# Adafruit_ESP32-S3_8MB_No_PSRAM.net
KiCad netlist of a schematic drawn in EAGLE
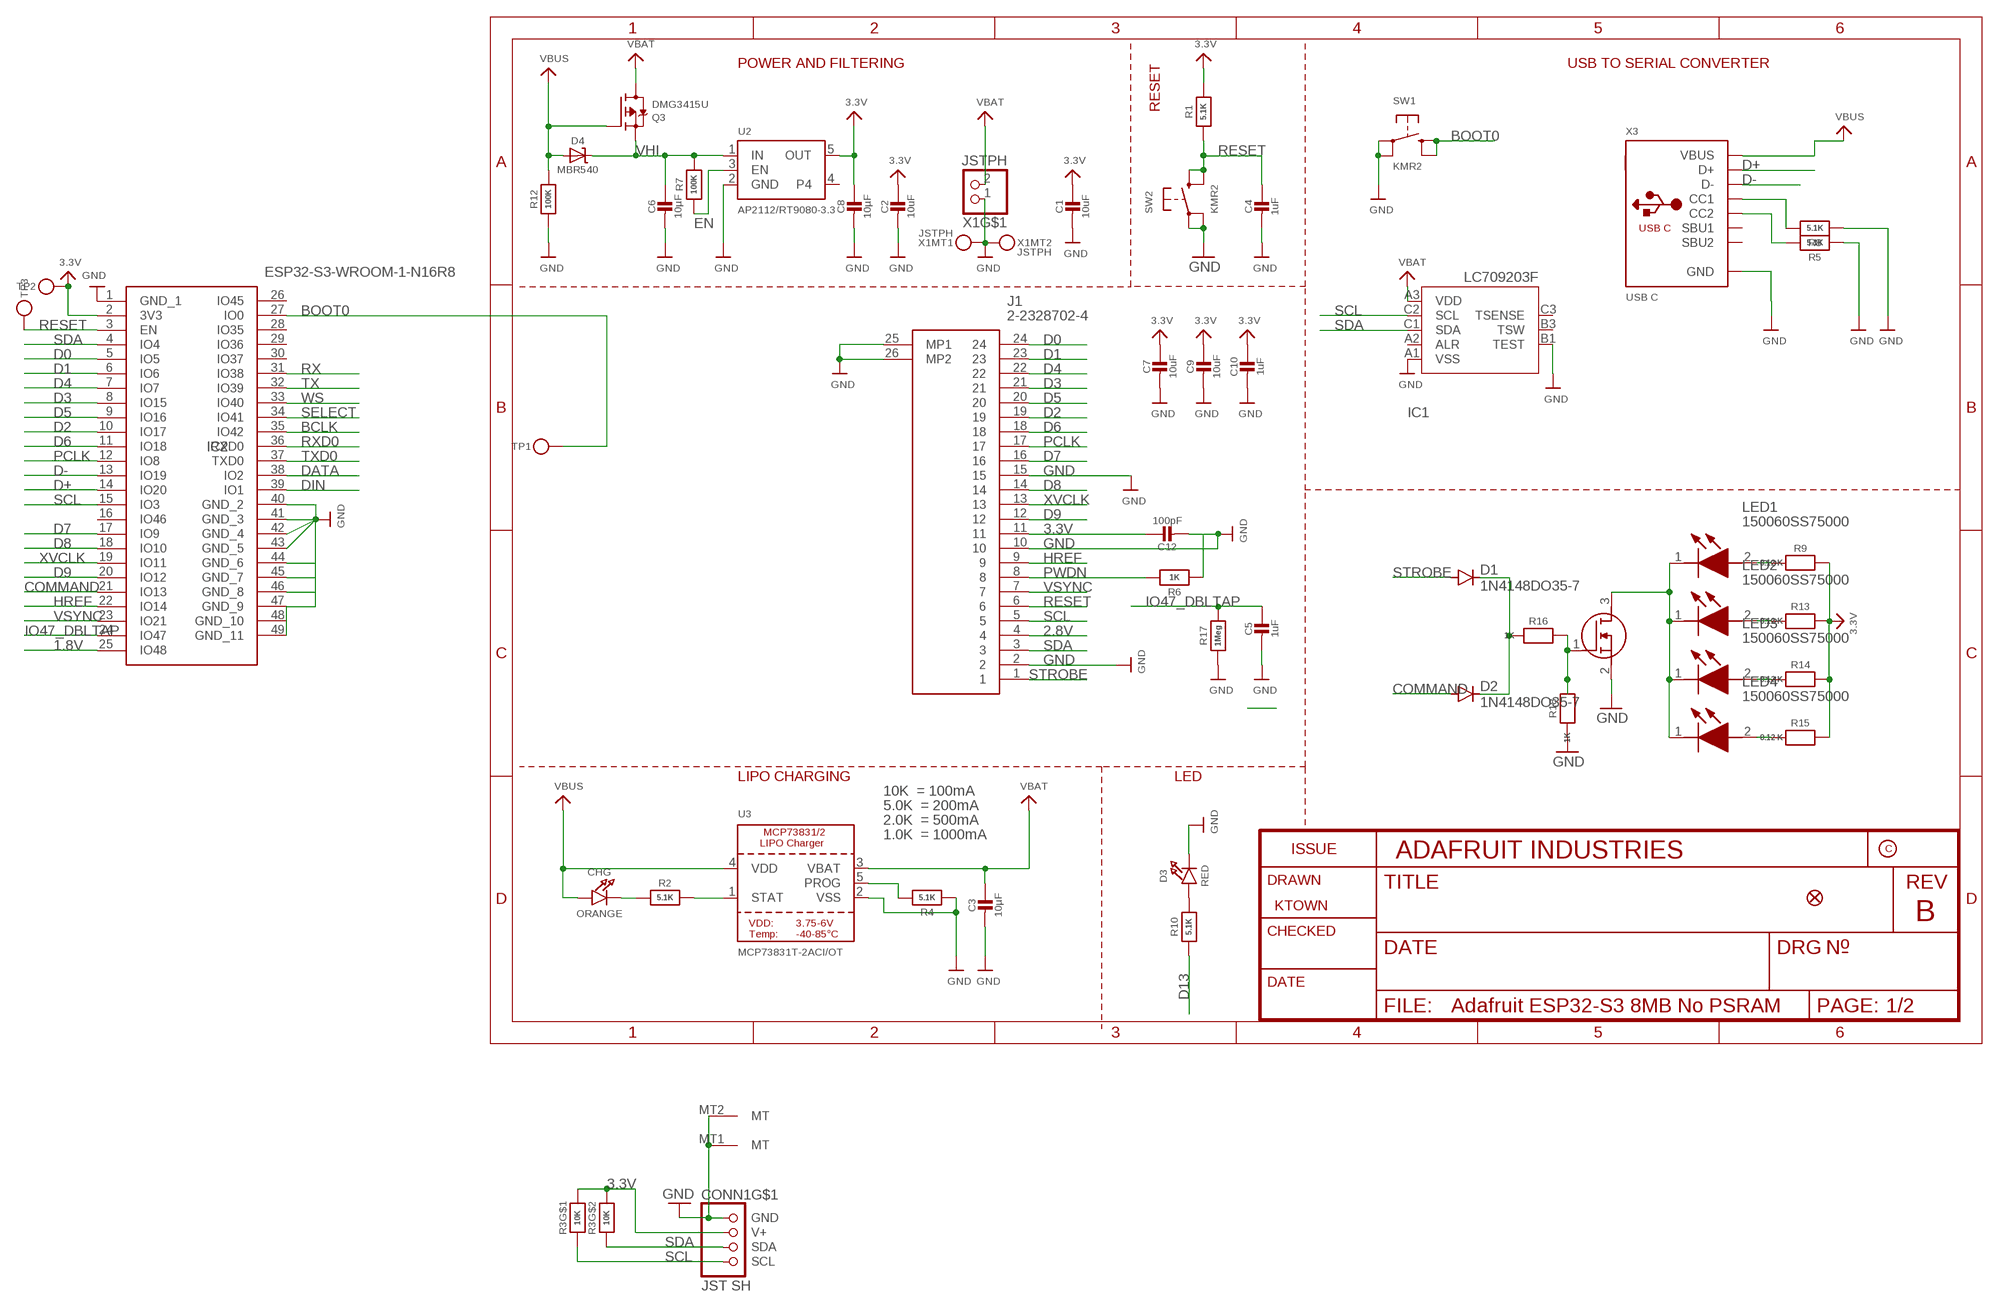
[diagram p0: schematic, sheet 1]
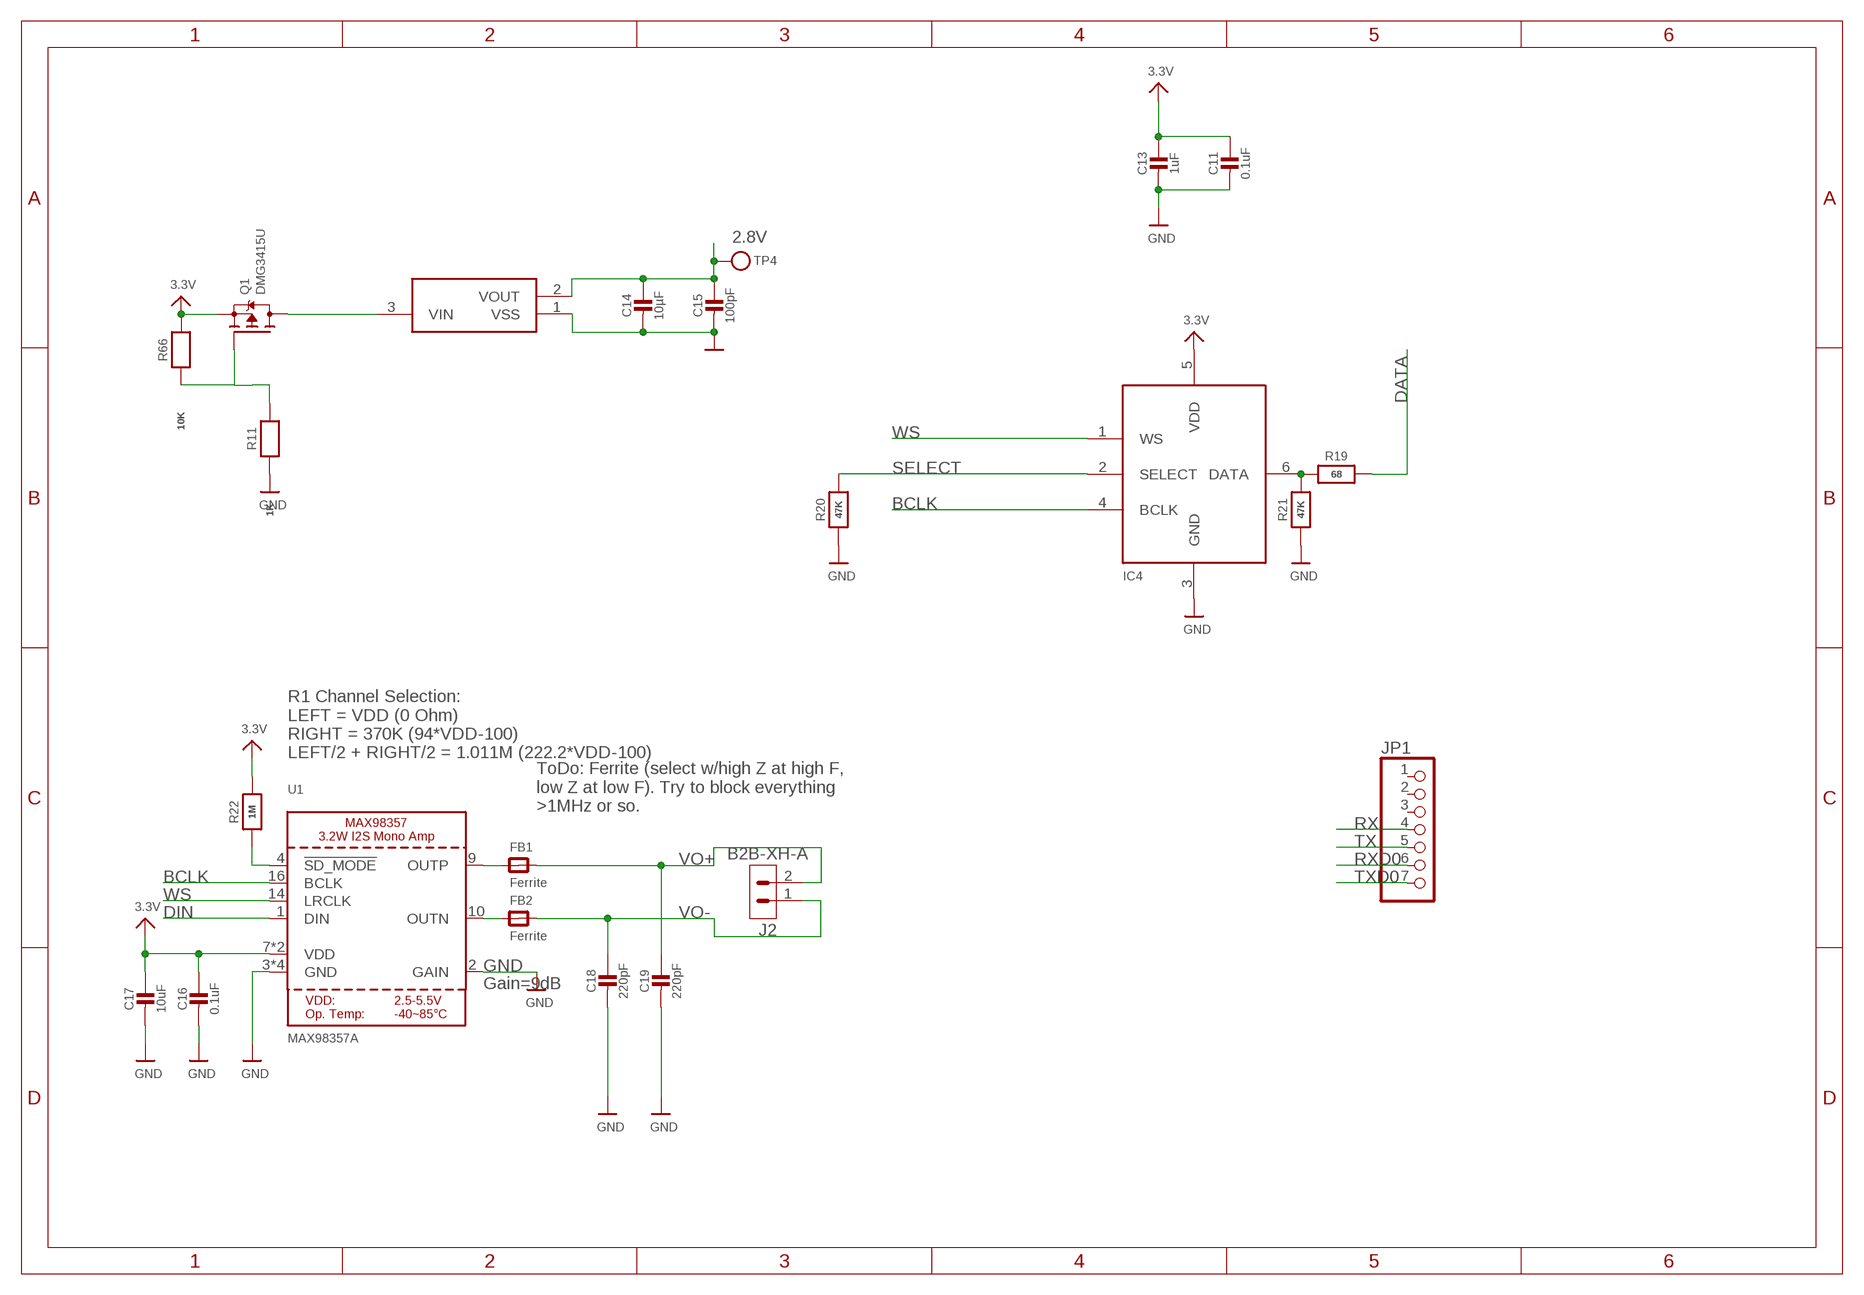
[diagram p1: schematic, sheet 2]

(export (version "E")
  (design (tool "Eeschema 10.0.6"))
  (components
    (comp (ref "C11")
      (value "0.1uF")
      (footprint "eagle-import:0603-NO")
      (libsource (lib "eagle-import") (part "CAP_CERAMIC0603_NO"))
    )
    (comp (ref "C13")
      (value "1uF")
      (footprint "eagle-import:0603-NO")
      (libsource (lib "eagle-import") (part "CAP_CERAMIC0603_NO"))
    )
    (comp (ref "C14")
      (value "10µF")
      (footprint "eagle-import:0805-NO")
      (libsource (lib "eagle-import") (part "CAP_CERAMIC0805-NOOUTLINE"))
    )
    (comp (ref "C15")
      (value "100pF")
      (footprint "eagle-import:0805-NO")
      (libsource (lib "eagle-import") (part "CAP_CERAMIC0805-NOOUTLINE"))
    )
    (comp (ref "C16")
      (value "0.1uF")
      (footprint "eagle-import:0805-NO")
      (libsource (lib "eagle-import") (part "CAP_CERAMIC0805-NOOUTLINE"))
    )
    (comp (ref "C17")
      (value "10uF")
      (footprint "eagle-import:0805-NO")
      (libsource (lib "eagle-import") (part "CAP_CERAMIC0805-NOOUTLINE"))
    )
    (comp (ref "C18")
      (value "220pF")
      (footprint "eagle-import:0805-NO")
      (libsource (lib "eagle-import") (part "CAP_CERAMIC0805-NOOUTLINE"))
    )
    (comp (ref "C19")
      (value "220pF")
      (footprint "eagle-import:0805-NO")
      (libsource (lib "eagle-import") (part "CAP_CERAMIC0805-NOOUTLINE"))
    )
    (comp (ref "FB1")
      (value "Ferrite")
      (footprint "eagle-import:0805-NO")
      (libsource (lib "eagle-import") (part "FERRITE-0805NO"))
    )
    (comp (ref "FB2")
      (value "Ferrite")
      (footprint "eagle-import:0805-NO")
      (libsource (lib "eagle-import") (part "FERRITE-0805NO"))
    )
    (comp (ref "IC3")
      (value "XC6206P282MR-G")
      (footprint "eagle-import:SOT95P280X130-3N")
      (fields (field (name "MOUSER_PART_NUMBER") "865-XC6206P282MR-G"))
      (libsource (lib "eagle-import") (part "XC6206P282MR-G"))
    )
    (comp (ref "IC4")
      (value "ICS-43434")
      (footprint "eagle-import:SPH0645LM4H")
      (libsource (lib "eagle-import") (part "MIC_I2S_SPH0645"))
    )
    (comp (ref "J2")
      (value "B2B-XH-A")
      (footprint "eagle-import:B2B-XH-A")
      (fields (field (name "MANUFACTURER") "JST Sales America Inc."))
      (libsource (lib "eagle-import") (part "B2B-XH-A"))
    )
    (comp (ref "JP1")
      (value "HEADER-1X7THICKER")
      (footprint "eagle-import:1X07_ROUND_76")
      (libsource (lib "eagle-import") (part "HEADER-1X7THICKER"))
    )
    (comp (ref "Q1")
      (value "DMG3415U")
      (footprint "eagle-import:SOT23-R")
      (libsource (lib "eagle-import") (part "MOSFET-P"))
    )
    (comp (ref "R11")
      (value "1K")
      (footprint "eagle-import:0603-NO")
      (libsource (lib "eagle-import") (part "RESISTOR_0603_NOOUT"))
    )
    (comp (ref "R19")
      (value "68")
      (footprint "eagle-import:0603-NO")
      (libsource (lib "eagle-import") (part "RESISTOR_0603_NOOUT"))
    )
    (comp (ref "R20")
      (value "47K")
      (footprint "eagle-import:0603-NO")
      (libsource (lib "eagle-import") (part "RESISTOR_0603_NOOUT"))
    )
    (comp (ref "R21")
      (value "47K")
      (footprint "eagle-import:0603-NO")
      (libsource (lib "eagle-import") (part "RESISTOR_0603_NOOUT"))
    )
    (comp (ref "R22")
      (value "1M")
      (footprint "eagle-import:0805-NO")
      (libsource (lib "eagle-import") (part "RESISTOR0805_NOOUTLINE"))
    )
    (comp (ref "R66")
      (value "10K")
      (footprint "eagle-import:0603-NO")
      (libsource (lib "eagle-import") (part "RESISTOR_0603_NOOUT"))
    )
    (comp (ref "TP4")
      (value "TESTPOINTROUND1.5MMNO")
      (footprint "eagle-import:TESTPOINT_ROUND_1.5MM_NO")
      (libsource (lib "eagle-import") (part "TESTPOINTROUND1.5MMNO"))
    )
    (comp (ref "U1")
      (value "MAX98357A")
      (footprint "eagle-import:QFN16_3MM")
      (libsource (lib "eagle-import") (part "AUDIOAMP_MAX98357"))
    )
    (comp (ref "C1")
      (value "10uF")
      (footprint "eagle-import:0805-NO")
      (libsource (lib "eagle-import") (part "CAP_CERAMIC0805-NOOUTLINE"))
    )
    (comp (ref "C2")
      (value "10uF")
      (footprint "eagle-import:0805-NO")
      (libsource (lib "eagle-import") (part "CAP_CERAMIC0805-NOOUTLINE"))
    )
    (comp (ref "C3")
      (value "10µF")
      (footprint "eagle-import:0805-NO")
      (libsource (lib "eagle-import") (part "CAP_CERAMIC0805-NOOUTLINE"))
    )
    (comp (ref "C4")
      (value "1uF")
      (footprint "eagle-import:0603-NO")
      (libsource (lib "eagle-import") (part "CAP_CERAMIC0603_NO"))
    )
    (comp (ref "C5")
      (value "1uF")
      (footprint "eagle-import:0603-NO")
      (libsource (lib "eagle-import") (part "CAP_CERAMIC0603_NO"))
    )
    (comp (ref "C6")
      (value "10µF")
      (footprint "eagle-import:0805-NO")
      (libsource (lib "eagle-import") (part "CAP_CERAMIC0805-NOOUTLINE"))
    )
    (comp (ref "C7")
      (value "10uF")
      (footprint "eagle-import:0805-NO")
      (libsource (lib "eagle-import") (part "CAP_CERAMIC0805-NOOUTLINE"))
    )
    (comp (ref "C8")
      (value "10µF")
      (footprint "eagle-import:0805-NO")
      (fields (field (name "REV") "C"))
      (libsource (lib "eagle-import") (part "CAP_CERAMIC0805-NOOUTLINE"))
    )
    (comp (ref "C9")
      (value "10uF")
      (footprint "eagle-import:0805-NO")
      (libsource (lib "eagle-import") (part "CAP_CERAMIC0805-NOOUTLINE"))
    )
    (comp (ref "C10")
      (value "1uF")
      (footprint "eagle-import:0603-NO")
      (libsource (lib "eagle-import") (part "CAP_CERAMIC0603_NO"))
    )
    (comp (ref "C12")
      (value "100pF")
      (footprint "eagle-import:0805-NO")
      (libsource (lib "eagle-import") (part "CAP_CERAMIC0805-NOOUTLINE"))
    )
    (comp (ref "CHG")
      (value "ORANGE")
      (footprint "eagle-import:CHIPLED_0603_NOOUTLINE")
      (libsource (lib "eagle-import") (part "LED0603_NOOUTLINE"))
    )
    (comp (ref "CONN1")
      (value "JST SH")
      (footprint "eagle-import:JST_SH4_RA")
      (libsource (lib "eagle-import") (part "STEMMA_I2C_QTRA"))
    )
    (comp (ref "D1")
      (value "1N4148DO35-7")
      (footprint "eagle-import:DO35-7")
      (libsource (lib "eagle-import") (part "1N4148DO35-7"))
    )
    (comp (ref "D2")
      (value "1N4148DO35-7")
      (footprint "eagle-import:DO35-7")
      (libsource (lib "eagle-import") (part "1N4148DO35-7"))
    )
    (comp (ref "D3")
      (value "RED")
      (footprint "eagle-import:CHIPLED_0603_NOOUTLINE")
      (libsource (lib "eagle-import") (part "LED0603_NOOUTLINE"))
    )
    (comp (ref "D4")
      (value "MBR540")
      (footprint "eagle-import:SOD-123")
      (libsource (lib "eagle-import") (part "DIODE-SCHOTTKYSOD-123"))
    )
    (comp (ref "IC1")
      (value "LC709203F/MH")
      (footprint "eagle-import:WLCSP9")
      (libsource (lib "eagle-import") (part "LC709203F/MH"))
    )
    (comp (ref "IC2")
      (value "ESP32-S3-WROOM-1-N16R8")
      (footprint "eagle-import:ESP32S3WROOM1N16R8")
      (fields (field (name "MOUSER_PART_NUMBER") "356-ESP32S3WRM1N16R8"))
      (libsource (lib "eagle-import") (part "ESP32-S3-WROOM-1-N16R8"))
    )
    (comp (ref "J1")
      (value "2-2328702-4")
      (footprint "eagle-import:223287024")
      (fields (field (name "MOUSER_PART_NUMBER") "571-2-2328702-4"))
      (libsource (lib "eagle-import") (part "2-2328702-4"))
    )
    (comp (ref "LED1")
      (value "150060SS75000")
      (footprint "eagle-import:LEDC1608X80N")
      (fields (field (name "MOUSER_PART_NUMBER") "710-150060SS75000"))
      (libsource (lib "eagle-import") (part "150060SS75000"))
    )
    (comp (ref "LED2")
      (value "150060SS75000")
      (footprint "eagle-import:LEDC1608X80N")
      (fields (field (name "MOUSER_PART_NUMBER") "710-150060SS75000"))
      (libsource (lib "eagle-import") (part "150060SS75000"))
    )
    (comp (ref "LED3")
      (value "150060SS75000")
      (footprint "eagle-import:LEDC1608X80N")
      (fields (field (name "MOUSER_PART_NUMBER") "710-150060SS75000"))
      (libsource (lib "eagle-import") (part "150060SS75000"))
    )
    (comp (ref "LED4")
      (value "150060SS75000")
      (footprint "eagle-import:LEDC1608X80N")
      (fields (field (name "MOUSER_PART_NUMBER") "710-150060SS75000"))
      (libsource (lib "eagle-import") (part "150060SS75000"))
    )
    (comp (ref "Q2")
      (value "2N7002")
      (footprint "eagle-import:SOT96P240X120-3N")
      (fields (field (name "MOUSER_PART_NUMBER") "512-2N7002"))
      (libsource (lib "eagle-import") (part "2N7002"))
    )
    (comp (ref "Q3")
      (value "DMG3415U")
      (footprint "eagle-import:SOT23-R")
      (libsource (lib "eagle-import") (part "MOSFET-P"))
    )
    (comp (ref "R1")
      (value "5.1K")
      (footprint "eagle-import:0603-NO")
      (libsource (lib "eagle-import") (part "RESISTOR_0603_NOOUT"))
    )
    (comp (ref "R2")
      (value "5.1K")
      (footprint "eagle-import:0603-NO")
      (libsource (lib "eagle-import") (part "RESISTOR_0603_NOOUT"))
    )
    (comp (ref "R3")
      (value "10K")
      (footprint "eagle-import:RESPACK_4X0603")
      (libsource (lib "eagle-import") (part "RESISTOR_4PACK"))
    )
    (comp (ref "R4")
      (value "5.1K")
      (footprint "eagle-import:0603-NO")
      (libsource (lib "eagle-import") (part "RESISTOR_0603_NOOUT"))
    )
    (comp (ref "R5")
      (value "5.1K")
      (footprint "eagle-import:0603-NO")
      (libsource (lib "eagle-import") (part "RESISTOR_0603_NOOUT"))
    )
    (comp (ref "R6")
      (value "1K")
      (footprint "eagle-import:0603-NO")
      (libsource (lib "eagle-import") (part "RESISTOR_0603_NOOUT"))
    )
    (comp (ref "R7")
      (value "100K")
      (footprint "eagle-import:0603-NO")
      (libsource (lib "eagle-import") (part "RESISTOR_0603_NOOUT"))
    )
    (comp (ref "R8")
      (value "5.1K")
      (footprint "eagle-import:0603-NO")
      (libsource (lib "eagle-import") (part "RESISTOR_0603_NOOUT"))
    )
    (comp (ref "R9")
      (value "0.12 K")
      (footprint "eagle-import:0603-NO")
      (libsource (lib "eagle-import") (part "RESISTOR_0603_NOOUT"))
    )
    (comp (ref "R10")
      (value "5.1K")
      (footprint "eagle-import:0603-NO")
      (libsource (lib "eagle-import") (part "RESISTOR_0603_NOOUT"))
    )
    (comp (ref "R12")
      (value "100K")
      (footprint "eagle-import:0603-NO")
      (libsource (lib "eagle-import") (part "RESISTOR_0603_NOOUT"))
    )
    (comp (ref "R13")
      (value "0.12 K")
      (footprint "eagle-import:0603-NO")
      (libsource (lib "eagle-import") (part "RESISTOR_0603_NOOUT"))
    )
    (comp (ref "R14")
      (value "0.12 K")
      (footprint "eagle-import:0603-NO")
      (libsource (lib "eagle-import") (part "RESISTOR_0603_NOOUT"))
    )
    (comp (ref "R15")
      (value "0.12 K")
      (footprint "eagle-import:0603-NO")
      (libsource (lib "eagle-import") (part "RESISTOR_0603_NOOUT"))
    )
    (comp (ref "R16")
      (value "1K")
      (footprint "eagle-import:0603-NO")
      (libsource (lib "eagle-import") (part "RESISTOR_0603_NOOUT"))
    )
    (comp (ref "R17")
      (value "1Meg")
      (footprint "eagle-import:0603-NO")
      (libsource (lib "eagle-import") (part "RESISTOR_0603_NOOUT"))
    )
    (comp (ref "R18")
      (value "1K")
      (footprint "eagle-import:0603-NO")
      (libsource (lib "eagle-import") (part "RESISTOR_0603_NOOUT"))
    )
    (comp (ref "SW1")
      (value "KMR2")
      (footprint "eagle-import:BTN_KMR2_4.6X2.8")
      (libsource (lib "eagle-import") (part "SWITCH_TACT_SMT4.6X2.8"))
    )
    (comp (ref "SW2")
      (value "KMR2")
      (footprint "eagle-import:BTN_KMR2_4.6X2.8")
      (libsource (lib "eagle-import") (part "SWITCH_TACT_SMT4.6X2.8"))
    )
    (comp (ref "TP1")
      (value "TESTPOINTROUND1.5MMNO")
      (footprint "eagle-import:TESTPOINT_ROUND_1.5MM_NO")
      (libsource (lib "eagle-import") (part "TESTPOINTROUND1.5MMNO"))
    )
    (comp (ref "TP2")
      (value "TESTPOINTROUND1.5MMNO")
      (footprint "eagle-import:TESTPOINT_ROUND_1.5MM_NO")
      (libsource (lib "eagle-import") (part "TESTPOINTROUND1.5MMNO"))
    )
    (comp (ref "TP3")
      (value "TESTPOINTROUND1.5MMNO")
      (footprint "eagle-import:TESTPOINT_ROUND_1.5MM_NO")
      (libsource (lib "eagle-import") (part "TESTPOINTROUND1.5MMNO"))
    )
    (comp (ref "U$34")
      (value "FIDUCIAL_1MM")
      (footprint "eagle-import:FIDUCIAL_1MM")
      (libsource (lib "eagle-import") (part "FIDUCIAL_1MM"))
    )
    (comp (ref "U2")
      (value "AP2112/RT9080-3.3")
      (footprint "eagle-import:SOT23-5")
      (libsource (lib "eagle-import") (part "VREG_SOT23-5"))
    )
    (comp (ref "U3")
      (value "MCP73831T-2ACI/OT")
      (footprint "eagle-import:SOT23-5")
      (libsource (lib "eagle-import") (part "MCP73831/2"))
    )
    (comp (ref "X1")
      (value "JSTPH")
      (footprint "eagle-import:JSTPH2_BATT")
      (libsource (lib "eagle-import") (part "CON_JST_PH_2PIN_MT_BATT"))
    )
    (comp (ref "X3")
      (value "USB C")
      (footprint "eagle-import:USB_C_CUSB31-CFM2AX-01-X")
      (libsource (lib "eagle-import") (part "USB_C"))
    )
  )
  (nets
    (net (code "1") (name "1.8V") (class "Default")
      (node (ref "IC2") (pin "25") (pinfunction "IO48_25") (pintype "bidirectional"))
    )
    (net (code "2") (name "2.8V") (class "Default")
      (node (ref "C14") (pin "1") (pinfunction "1_1") (pintype "passive"))
      (node (ref "C15") (pin "1") (pinfunction "1_1") (pintype "passive"))
      (node (ref "IC3") (pin "2") (pinfunction "VOUT_2") (pintype "bidirectional"))
      (node (ref "J1") (pin "4") (pinfunction "4_4") (pintype "bidirectional"))
      (node (ref "TP4") (pin "P$1") (pinfunction "P$1_P$1") (pintype "bidirectional"))
    )
    (net (code "3") (name "3.3V") (class "Default")
      (node (ref "C1") (pin "1") (pinfunction "1_1") (pintype "passive"))
      (node (ref "C10") (pin "1") (pinfunction "1_1") (pintype "passive"))
      (node (ref "C11") (pin "1") (pinfunction "1_1") (pintype "passive"))
      (node (ref "C12") (pin "1") (pinfunction "1_1") (pintype "passive"))
      (node (ref "C13") (pin "1") (pinfunction "1_1") (pintype "passive"))
      (node (ref "C16") (pin "1") (pinfunction "1_1") (pintype "passive"))
      (node (ref "C17") (pin "1") (pinfunction "1_1") (pintype "passive"))
      (node (ref "C2") (pin "1") (pinfunction "1_1") (pintype "passive"))
      (node (ref "C7") (pin "1") (pinfunction "1_1") (pintype "passive"))
      (node (ref "C8") (pin "1") (pinfunction "1_1") (pintype "passive"))
      (node (ref "C9") (pin "1") (pinfunction "1_1") (pintype "passive"))
      (node (ref "CONN1") (pin "2") (pinfunction "V+_2") (pintype "passive"))
      (node (ref "IC2") (pin "2") (pinfunction "3V3_2") (pintype "bidirectional"))
      (node (ref "IC4") (pin "5") (pinfunction "VDD_5") (pintype "power_in"))
      (node (ref "J1") (pin "11") (pinfunction "11_11") (pintype "bidirectional"))
      (node (ref "Q1") (pin "2") (pinfunction "S_2") (pintype "passive"))
      (node (ref "R1") (pin "2") (pinfunction "2_2") (pintype "passive"))
      (node (ref "R13") (pin "2") (pinfunction "2_2") (pintype "passive"))
      (node (ref "R14") (pin "2") (pinfunction "2_2") (pintype "passive"))
      (node (ref "R15") (pin "2") (pinfunction "2_2") (pintype "passive"))
      (node (ref "R22") (pin "2") (pinfunction "2_2") (pintype "passive"))
      (node (ref "R3") (pin "7") (pinfunction "2_7") (pintype "passive"))
      (node (ref "R3") (pin "8") (pinfunction "2_8") (pintype "passive"))
      (node (ref "R66") (pin "2") (pinfunction "2_2") (pintype "passive"))
      (node (ref "R9") (pin "2") (pinfunction "2_2") (pintype "passive"))
      (node (ref "TP2") (pin "P$1") (pinfunction "P$1_P$1") (pintype "bidirectional"))
      (node (ref "U1") (pin "7") (pinfunction "VDD_7") (pintype "power_in"))
      (node (ref "U1") (pin "8") (pinfunction "VDD_8") (pintype "power_in"))
      (node (ref "U2") (pin "5") (pinfunction "OUT_5") (pintype "power_in"))
    )
    (net (code "4") (name "BCLK") (class "Default")
      (node (ref "IC2") (pin "35") (pinfunction "IO42_35") (pintype "bidirectional"))
      (node (ref "IC4") (pin "4") (pinfunction "BCLK_4") (pintype "input"))
      (node (ref "U1") (pin "16") (pinfunction "BCLK_16") (pintype "bidirectional"))
    )
    (net (code "5") (name "BOOT0") (class "Default")
      (node (ref "IC2") (pin "27") (pinfunction "IO0_27") (pintype "bidirectional"))
      (node (ref "SW1") (pin "B") (pinfunction "S_B") (pintype "passive"))
      (node (ref "SW1") (pin "B'") (pinfunction "S1_B'") (pintype "passive"))
      (node (ref "TP1") (pin "P$1") (pinfunction "P$1_P$1") (pintype "bidirectional"))
    )
    (net (code "6") (name "COMMAND") (class "Default")
      (node (ref "D2") (pin "A") (pinfunction "A_A") (pintype "passive"))
      (node (ref "IC2") (pin "21") (pinfunction "IO13_21") (pintype "bidirectional"))
    )
    (net (code "7") (name "D+") (class "Default")
      (node (ref "IC2") (pin "14") (pinfunction "IO20_14") (pintype "bidirectional"))
      (node (ref "X3") (pin "A6") (pinfunction "D+_A6") (pintype "bidirectional"))
      (node (ref "X3") (pin "B6") (pinfunction "D+_B6") (pintype "bidirectional"))
    )
    (net (code "8") (name "D-") (class "Default")
      (node (ref "IC2") (pin "13") (pinfunction "IO19_13") (pintype "bidirectional"))
      (node (ref "X3") (pin "A7") (pinfunction "D-_A7") (pintype "bidirectional"))
      (node (ref "X3") (pin "B7") (pinfunction "D-_B7") (pintype "bidirectional"))
    )
    (net (code "9") (name "D0") (class "Default")
      (node (ref "IC2") (pin "5") (pinfunction "IO5_5") (pintype "bidirectional"))
      (node (ref "J1") (pin "24") (pinfunction "24_24") (pintype "bidirectional"))
    )
    (net (code "10") (name "D1") (class "Default")
      (node (ref "IC2") (pin "6") (pinfunction "IO6_6") (pintype "bidirectional"))
      (node (ref "J1") (pin "23") (pinfunction "23_23") (pintype "bidirectional"))
    )
    (net (code "11") (name "D2") (class "Default")
      (node (ref "IC2") (pin "10") (pinfunction "IO17_10") (pintype "bidirectional"))
      (node (ref "J1") (pin "19") (pinfunction "19_19") (pintype "bidirectional"))
    )
    (net (code "12") (name "D3") (class "Default")
      (node (ref "IC2") (pin "8") (pinfunction "IO15_8") (pintype "bidirectional"))
      (node (ref "J1") (pin "21") (pinfunction "21_21") (pintype "bidirectional"))
    )
    (net (code "13") (name "D4") (class "Default")
      (node (ref "IC2") (pin "7") (pinfunction "IO7_7") (pintype "bidirectional"))
      (node (ref "J1") (pin "22") (pinfunction "22_22") (pintype "bidirectional"))
    )
    (net (code "14") (name "D5") (class "Default")
      (node (ref "IC2") (pin "9") (pinfunction "IO16_9") (pintype "bidirectional"))
      (node (ref "J1") (pin "20") (pinfunction "20_20") (pintype "bidirectional"))
    )
    (net (code "15") (name "D6") (class "Default")
      (node (ref "IC2") (pin "11") (pinfunction "IO18_11") (pintype "bidirectional"))
      (node (ref "J1") (pin "18") (pinfunction "18_18") (pintype "bidirectional"))
    )
    (net (code "16") (name "D7") (class "Default")
      (node (ref "IC2") (pin "17") (pinfunction "IO9_17") (pintype "bidirectional"))
      (node (ref "J1") (pin "16") (pinfunction "16_16") (pintype "bidirectional"))
    )
    (net (code "17") (name "D8") (class "Default")
      (node (ref "IC2") (pin "18") (pinfunction "IO10_18") (pintype "bidirectional"))
      (node (ref "J1") (pin "14") (pinfunction "14_14") (pintype "bidirectional"))
    )
    (net (code "18") (name "D9") (class "Default")
      (node (ref "IC2") (pin "20") (pinfunction "IO12_20") (pintype "bidirectional"))
      (node (ref "J1") (pin "12") (pinfunction "12_12") (pintype "bidirectional"))
    )
    (net (code "19") (name "D13") (class "Default")
      (node (ref "R10") (pin "1") (pinfunction "1_1") (pintype "passive"))
    )
    (net (code "20") (name "DATA") (class "Default")
      (node (ref "IC2") (pin "38") (pinfunction "IO2_38") (pintype "bidirectional"))
      (node (ref "R19") (pin "2") (pinfunction "2_2") (pintype "passive"))
    )
    (net (code "21") (name "DIN") (class "Default")
      (node (ref "IC2") (pin "39") (pinfunction "IO1_39") (pintype "bidirectional"))
      (node (ref "U1") (pin "1") (pinfunction "DIN_1") (pintype "bidirectional"))
    )
    (net (code "22") (name "EN") (class "Default")
      (node (ref "R7") (pin "1") (pinfunction "1_1") (pintype "passive"))
      (node (ref "U2") (pin "3") (pinfunction "EN_3") (pintype "input"))
    )
    (net (code "23") (name "GND") (class "Default")
      (node (ref "C1") (pin "2") (pinfunction "2_2") (pintype "passive"))
      (node (ref "C10") (pin "2") (pinfunction "2_2") (pintype "passive"))
      (node (ref "C11") (pin "2") (pinfunction "2_2") (pintype "passive"))
      (node (ref "C12") (pin "2") (pinfunction "2_2") (pintype "passive"))
      (node (ref "C13") (pin "2") (pinfunction "2_2") (pintype "passive"))
      (node (ref "C14") (pin "2") (pinfunction "2_2") (pintype "passive"))
      (node (ref "C15") (pin "2") (pinfunction "2_2") (pintype "passive"))
      (node (ref "C16") (pin "2") (pinfunction "2_2") (pintype "passive"))
      (node (ref "C17") (pin "2") (pinfunction "2_2") (pintype "passive"))
      (node (ref "C18") (pin "2") (pinfunction "2_2") (pintype "passive"))
      (node (ref "C19") (pin "2") (pinfunction "2_2") (pintype "passive"))
      (node (ref "C2") (pin "2") (pinfunction "2_2") (pintype "passive"))
      (node (ref "C3") (pin "2") (pinfunction "2_2") (pintype "passive"))
      (node (ref "C4") (pin "2") (pinfunction "2_2") (pintype "passive"))
      (node (ref "C5") (pin "2") (pinfunction "2_2") (pintype "passive"))
      (node (ref "C6") (pin "2") (pinfunction "2_2") (pintype "passive"))
      (node (ref "C7") (pin "2") (pinfunction "2_2") (pintype "passive"))
      (node (ref "C8") (pin "2") (pinfunction "2_2") (pintype "passive"))
      (node (ref "C9") (pin "2") (pinfunction "2_2") (pintype "passive"))
      (node (ref "CONN1") (pin "1") (pinfunction "GND_1") (pintype "passive"))
      (node (ref "CONN1") (pin "MT1") (pinfunction "MT_MT1") (pintype "bidirectional"))
      (node (ref "CONN1") (pin "MT2") (pinfunction "MT_MT2") (pintype "bidirectional"))
      (node (ref "D3") (pin "C") (pinfunction "C_C") (pintype "passive"))
      (node (ref "IC1") (pin "A1") (pinfunction "VSS_A1") (pintype "power_in"))
      (node (ref "IC1") (pin "B1") (pinfunction "TEST_B1") (pintype "input"))
      (node (ref "IC2") (pin "1") (pinfunction "GND_1_1") (pintype "bidirectional"))
      (node (ref "IC2") (pin "40") (pinfunction "GND_2_40") (pintype "bidirectional"))
      (node (ref "IC2") (pin "41") (pinfunction "GND_3_41") (pintype "bidirectional"))
      (node (ref "IC2") (pin "42") (pinfunction "GND_4_42") (pintype "bidirectional"))
      (node (ref "IC2") (pin "43") (pinfunction "GND_5_43") (pintype "bidirectional"))
      (node (ref "IC2") (pin "44") (pinfunction "GND_6_44") (pintype "bidirectional"))
      (node (ref "IC2") (pin "45") (pinfunction "GND_7_45") (pintype "bidirectional"))
      (node (ref "IC2") (pin "46") (pinfunction "GND_8_46") (pintype "bidirectional"))
      (node (ref "IC2") (pin "47") (pinfunction "GND_9_47") (pintype "bidirectional"))
      (node (ref "IC2") (pin "48") (pinfunction "GND_10_48") (pintype "bidirectional"))
      (node (ref "IC2") (pin "49") (pinfunction "GND_11_49") (pintype "bidirectional"))
      (node (ref "IC3") (pin "1") (pinfunction "VSS_1") (pintype "bidirectional"))
      (node (ref "IC4") (pin "3") (pinfunction "GND_3") (pintype "power_in"))
      (node (ref "J1") (pin "10") (pinfunction "10_10") (pintype "bidirectional"))
      (node (ref "J1") (pin "15") (pinfunction "15_15") (pintype "bidirectional"))
      (node (ref "J1") (pin "2") (pinfunction "2_2") (pintype "bidirectional"))
      (node (ref "J1") (pin "25") (pinfunction "MP1_25") (pintype "bidirectional"))
      (node (ref "J1") (pin "26") (pinfunction "MP2_26") (pintype "bidirectional"))
      (node (ref "Q2") (pin "2") (pinfunction "S_2") (pintype "bidirectional"))
      (node (ref "R11") (pin "1") (pinfunction "1_1") (pintype "passive"))
      (node (ref "R12") (pin "1") (pinfunction "1_1") (pintype "passive"))
      (node (ref "R17") (pin "1") (pinfunction "1_1") (pintype "passive"))
      (node (ref "R18") (pin "1") (pinfunction "1_1") (pintype "passive"))
      (node (ref "R20") (pin "1") (pinfunction "1_1") (pintype "passive"))
      (node (ref "R21") (pin "1") (pinfunction "1_1") (pintype "passive"))
      (node (ref "R4") (pin "1") (pinfunction "1_1") (pintype "passive"))
      (node (ref "R5") (pin "1") (pinfunction "1_1") (pintype "passive"))
      (node (ref "R6") (pin "1") (pinfunction "1_1") (pintype "passive"))
      (node (ref "R8") (pin "1") (pinfunction "1_1") (pintype "passive"))
      (node (ref "SW1") (pin "A") (pinfunction "P_A") (pintype "passive"))
      (node (ref "SW1") (pin "A'") (pinfunction "P1_A'") (pintype "passive"))
      (node (ref "SW2") (pin "A") (pinfunction "P_A") (pintype "passive"))
      (node (ref "SW2") (pin "A'") (pinfunction "P1_A'") (pintype "passive"))
      (node (ref "U1") (pin "11") (pinfunction "GND_11") (pintype "power_in"))
      (node (ref "U1") (pin "15") (pinfunction "GND_15") (pintype "power_in"))
      (node (ref "U1") (pin "2") (pinfunction "GAIN_2") (pintype "bidirectional"))
      (node (ref "U1") (pin "3") (pinfunction "GND_3") (pintype "power_in"))
      (node (ref "U1") (pin "THERMAL") (pinfunction "GND_THERMAL") (pintype "power_in"))
      (node (ref "U2") (pin "2") (pinfunction "GND_2") (pintype "power_in"))
      (node (ref "U3") (pin "2") (pinfunction "VSS_2") (pintype "power_in"))
      (node (ref "X1") (pin "1") (pinfunction "1_1") (pintype "passive"))
      (node (ref "X1") (pin "NC1") (pinfunction "P$1_NC1") (pintype "bidirectional"))
      (node (ref "X1") (pin "NC2") (pinfunction "P$1_NC2") (pintype "bidirectional"))
      (node (ref "X3") (pin "A1B12") (pinfunction "GND_A1B12") (pintype "power_in"))
      (node (ref "X3") (pin "B1A12") (pinfunction "GND_B1A12") (pintype "power_in"))
    )
    (net (code "24") (name "HREF") (class "Default")
      (node (ref "IC2") (pin "22") (pinfunction "IO14_22") (pintype "bidirectional"))
      (node (ref "J1") (pin "9") (pinfunction "9_9") (pintype "bidirectional"))
    )
    (net (code "25") (name "IO47_DBLTAP") (class "Default")
      (node (ref "C5") (pin "1") (pinfunction "1_1") (pintype "passive"))
      (node (ref "IC2") (pin "24") (pinfunction "IO47_24") (pintype "bidirectional"))
      (node (ref "R17") (pin "2") (pinfunction "2_2") (pintype "passive"))
    )
    (net (code "26") (name "Net-(CHG-PadC)") (class "Default")
      (node (ref "CHG") (pin "C") (pinfunction "C_C") (pintype "passive"))
      (node (ref "R2") (pin "1") (pinfunction "1_1") (pintype "passive"))
    )
    (net (code "27") (name "Net-(D1-PadC)") (class "Default")
      (node (ref "D1") (pin "C") (pinfunction "C_C") (pintype "passive"))
      (node (ref "D2") (pin "C") (pinfunction "C_C") (pintype "passive"))
      (node (ref "R16") (pin "1") (pinfunction "1_1") (pintype "passive"))
    )
    (net (code "28") (name "Net-(D3-PadA)") (class "Default")
      (node (ref "D3") (pin "A") (pinfunction "A_A") (pintype "passive"))
      (node (ref "R10") (pin "2") (pinfunction "2_2") (pintype "passive"))
    )
    (net (code "29") (name "Net-(FB1-P$1)") (class "Default")
      (node (ref "FB1") (pin "1") (pinfunction "P$1_1") (pintype "passive"))
      (node (ref "U1") (pin "9") (pinfunction "OUTP_9") (pintype "output"))
    )
    (net (code "30") (name "Net-(FB2-P$1)") (class "Default")
      (node (ref "FB2") (pin "1") (pinfunction "P$1_1") (pintype "passive"))
      (node (ref "U1") (pin "10") (pinfunction "OUTN_10") (pintype "output"))
    )
    (net (code "31") (name "Net-(IC3-VIN)") (class "Default")
      (node (ref "IC3") (pin "3") (pinfunction "VIN_3") (pintype "bidirectional"))
      (node (ref "Q1") (pin "3") (pinfunction "D_3") (pintype "passive"))
    )
    (net (code "32") (name "Net-(IC4-DATA)") (class "Default")
      (node (ref "IC4") (pin "6") (pinfunction "DATA_6") (pintype "output"))
      (node (ref "R19") (pin "1") (pinfunction "1_1") (pintype "passive"))
      (node (ref "R21") (pin "2") (pinfunction "2_2") (pintype "passive"))
    )
    (net (code "33") (name "Net-(LED1-A)") (class "Default")
      (node (ref "LED1") (pin "2") (pinfunction "A_2") (pintype "bidirectional"))
      (node (ref "R9") (pin "1") (pinfunction "1_1") (pintype "passive"))
    )
    (net (code "34") (name "Net-(LED1-K)") (class "Default")
      (node (ref "LED1") (pin "1") (pinfunction "K_1") (pintype "bidirectional"))
      (node (ref "LED2") (pin "1") (pinfunction "K_1") (pintype "bidirectional"))
      (node (ref "LED3") (pin "1") (pinfunction "K_1") (pintype "bidirectional"))
      (node (ref "LED4") (pin "1") (pinfunction "K_1") (pintype "bidirectional"))
      (node (ref "Q2") (pin "3") (pinfunction "D_3") (pintype "bidirectional"))
    )
    (net (code "35") (name "Net-(LED2-A)") (class "Default")
      (node (ref "LED2") (pin "2") (pinfunction "A_2") (pintype "bidirectional"))
      (node (ref "R13") (pin "1") (pinfunction "1_1") (pintype "passive"))
    )
    (net (code "36") (name "Net-(LED3-A)") (class "Default")
      (node (ref "LED3") (pin "2") (pinfunction "A_2") (pintype "bidirectional"))
      (node (ref "R14") (pin "1") (pinfunction "1_1") (pintype "passive"))
    )
    (net (code "37") (name "Net-(LED4-A)") (class "Default")
      (node (ref "LED4") (pin "2") (pinfunction "A_2") (pintype "bidirectional"))
      (node (ref "R15") (pin "1") (pinfunction "1_1") (pintype "passive"))
    )
    (net (code "38") (name "Net-(Q1-G)") (class "Default")
      (node (ref "Q1") (pin "1") (pinfunction "G_1") (pintype "passive"))
      (node (ref "R11") (pin "2") (pinfunction "2_2") (pintype "passive"))
      (node (ref "R66") (pin "1") (pinfunction "1_1") (pintype "passive"))
    )
    (net (code "39") (name "Net-(Q2-G)") (class "Default")
      (node (ref "Q2") (pin "1") (pinfunction "G_1") (pintype "bidirectional"))
      (node (ref "R16") (pin "2") (pinfunction "2_2") (pintype "passive"))
      (node (ref "R18") (pin "2") (pinfunction "2_2") (pintype "passive"))
    )
    (net (code "40") (name "Net-(U1-~{SD_MODE})") (class "Default")
      (node (ref "R22") (pin "1") (pinfunction "1_1") (pintype "passive"))
      (node (ref "U1") (pin "4") (pinfunction "~{SD_MODE}_4") (pintype "bidirectional"))
    )
    (net (code "41") (name "Net-(U3-PROG)") (class "Default")
      (node (ref "R4") (pin "2") (pinfunction "2_2") (pintype "passive"))
      (node (ref "U3") (pin "5") (pinfunction "PROG_5") (pintype "input"))
    )
    (net (code "42") (name "Net-(U3-STAT)") (class "Default")
      (node (ref "R2") (pin "2") (pinfunction "2_2") (pintype "passive"))
      (node (ref "U3") (pin "1") (pinfunction "STAT_1") (pintype "output"))
    )
    (net (code "43") (name "Net-(X3-CC1)") (class "Default")
      (node (ref "R8") (pin "2") (pinfunction "2_2") (pintype "passive"))
      (node (ref "X3") (pin "A5") (pinfunction "CC1_A5") (pintype "bidirectional"))
    )
    (net (code "44") (name "Net-(X3-CC2)") (class "Default")
      (node (ref "R5") (pin "2") (pinfunction "2_2") (pintype "passive"))
      (node (ref "X3") (pin "B5") (pinfunction "CC2_B5") (pintype "bidirectional"))
    )
    (net (code "45") (name "PCLK") (class "Default")
      (node (ref "IC2") (pin "12") (pinfunction "IO8_12") (pintype "bidirectional"))
      (node (ref "J1") (pin "17") (pinfunction "17_17") (pintype "bidirectional"))
    )
    (net (code "46") (name "PWDN") (class "Default")
      (node (ref "J1") (pin "8") (pinfunction "8_8") (pintype "bidirectional"))
      (node (ref "R6") (pin "2") (pinfunction "2_2") (pintype "passive"))
    )
    (net (code "47") (name "RESET") (class "Default")
      (node (ref "C4") (pin "1") (pinfunction "1_1") (pintype "passive"))
      (node (ref "IC2") (pin "3") (pinfunction "EN_3") (pintype "bidirectional"))
      (node (ref "J1") (pin "6") (pinfunction "6_6") (pintype "bidirectional"))
      (node (ref "R1") (pin "1") (pinfunction "1_1") (pintype "passive"))
      (node (ref "SW2") (pin "B") (pinfunction "S_B") (pintype "passive"))
      (node (ref "SW2") (pin "B'") (pinfunction "S1_B'") (pintype "passive"))
      (node (ref "TP3") (pin "P$1") (pinfunction "P$1_P$1") (pintype "bidirectional"))
    )
    (net (code "48") (name "RX") (class "Default")
      (node (ref "IC2") (pin "31") (pinfunction "IO38_31") (pintype "bidirectional"))
      (node (ref "JP1") (pin "4") (pinfunction "4_4") (pintype "passive"))
    )
    (net (code "49") (name "RXD0") (class "Default")
      (node (ref "IC2") (pin "36") (pinfunction "RXD0_36") (pintype "bidirectional"))
      (node (ref "JP1") (pin "6") (pinfunction "6_6") (pintype "passive"))
    )
    (net (code "50") (name "SCL") (class "Default")
      (node (ref "CONN1") (pin "4") (pinfunction "SCL_4") (pintype "passive"))
      (node (ref "IC1") (pin "C2") (pinfunction "SCL_C2") (pintype "bidirectional"))
      (node (ref "IC2") (pin "15") (pinfunction "IO3_15") (pintype "bidirectional"))
      (node (ref "J1") (pin "5") (pinfunction "5_5") (pintype "bidirectional"))
      (node (ref "R3") (pin "1") (pinfunction "1_1") (pintype "passive"))
    )
    (net (code "51") (name "SDA") (class "Default")
      (node (ref "CONN1") (pin "3") (pinfunction "SDA_3") (pintype "passive"))
      (node (ref "IC1") (pin "C1") (pinfunction "SDA_C1") (pintype "bidirectional"))
      (node (ref "IC2") (pin "4") (pinfunction "IO4_4") (pintype "bidirectional"))
      (node (ref "J1") (pin "3") (pinfunction "3_3") (pintype "bidirectional"))
      (node (ref "R3") (pin "2") (pinfunction "1_2") (pintype "passive"))
    )
    (net (code "52") (name "SELECT") (class "Default")
      (node (ref "IC2") (pin "34") (pinfunction "IO41_34") (pintype "bidirectional"))
      (node (ref "IC4") (pin "2") (pinfunction "SELECT_2") (pintype "input"))
      (node (ref "R20") (pin "2") (pinfunction "2_2") (pintype "passive"))
    )
    (net (code "53") (name "STROBE") (class "Default")
      (node (ref "D1") (pin "A") (pinfunction "A_A") (pintype "passive"))
      (node (ref "J1") (pin "1") (pinfunction "1_1") (pintype "bidirectional"))
    )
    (net (code "54") (name "TX") (class "Default")
      (node (ref "IC2") (pin "32") (pinfunction "IO39_32") (pintype "bidirectional"))
      (node (ref "JP1") (pin "5") (pinfunction "5_5") (pintype "passive"))
    )
    (net (code "55") (name "TXD0") (class "Default")
      (node (ref "IC2") (pin "37") (pinfunction "TXD0_37") (pintype "bidirectional"))
      (node (ref "JP1") (pin "7") (pinfunction "7_7") (pintype "passive"))
    )
    (net (code "56") (name "VBAT") (class "Default")
      (node (ref "C3") (pin "1") (pinfunction "1_1") (pintype "passive"))
      (node (ref "IC1") (pin "A3") (pinfunction "VDD_A3") (pintype "power_in"))
      (node (ref "Q3") (pin "3") (pinfunction "D_3") (pintype "passive"))
      (node (ref "U3") (pin "3") (pinfunction "VBAT_3") (pintype "power_in"))
      (node (ref "X1") (pin "2") (pinfunction "2_2") (pintype "passive"))
    )
    (net (code "57") (name "VBUS") (class "Default")
      (node (ref "CHG") (pin "A") (pinfunction "A_A") (pintype "passive"))
      (node (ref "D4") (pin "A") (pinfunction "A_A") (pintype "passive"))
      (node (ref "Q3") (pin "1") (pinfunction "G_1") (pintype "passive"))
      (node (ref "R12") (pin "2") (pinfunction "2_2") (pintype "passive"))
      (node (ref "U3") (pin "4") (pinfunction "VDD_4") (pintype "power_in"))
      (node (ref "X3") (pin "A4B9") (pinfunction "VBUS_A4B9") (pintype "power_in"))
      (node (ref "X3") (pin "B4A9") (pinfunction "VBUS_B4A9") (pintype "power_in"))
    )
    (net (code "58") (name "VHI") (class "Default")
      (node (ref "C6") (pin "1") (pinfunction "1_1") (pintype "passive"))
      (node (ref "D4") (pin "C") (pinfunction "C_C") (pintype "passive"))
      (node (ref "Q3") (pin "2") (pinfunction "S_2") (pintype "passive"))
      (node (ref "R7") (pin "2") (pinfunction "2_2") (pintype "passive"))
      (node (ref "U2") (pin "1") (pinfunction "IN_1") (pintype "power_in"))
    )
    (net (code "59") (name "VO+") (class "Default")
      (node (ref "C19") (pin "1") (pinfunction "1_1") (pintype "passive"))
      (node (ref "FB1") (pin "2") (pinfunction "P$2_2") (pintype "passive"))
      (node (ref "J2") (pin "2") (pinfunction "2_2") (pintype "passive"))
    )
    (net (code "60") (name "VO-") (class "Default")
      (node (ref "C18") (pin "1") (pinfunction "1_1") (pintype "passive"))
      (node (ref "FB2") (pin "2") (pinfunction "P$2_2") (pintype "passive"))
      (node (ref "J2") (pin "1") (pinfunction "1_1") (pintype "passive"))
    )
    (net (code "61") (name "VSYNC") (class "Default")
      (node (ref "IC2") (pin "23") (pinfunction "IO21_23") (pintype "bidirectional"))
      (node (ref "J1") (pin "7") (pinfunction "7_7") (pintype "bidirectional"))
    )
    (net (code "62") (name "WS") (class "Default")
      (node (ref "IC2") (pin "33") (pinfunction "IO40_33") (pintype "bidirectional"))
      (node (ref "IC4") (pin "1") (pinfunction "WS_1") (pintype "input"))
      (node (ref "U1") (pin "14") (pinfunction "LRCLK_14") (pintype "bidirectional"))
    )
    (net (code "63") (name "XVCLK") (class "Default")
      (node (ref "IC2") (pin "19") (pinfunction "IO11_19") (pintype "bidirectional"))
      (node (ref "J1") (pin "13") (pinfunction "13_13") (pintype "bidirectional"))
    )
    (net (code "64") (name "unconnected-(IC1-ALR-PadA2)") (class "Default")
      (node (ref "IC1") (pin "A2") (pinfunction "ALR_A2") (pintype "output"))
    )
    (net (code "65") (name "unconnected-(IC1-TSENSE-PadC3)") (class "Default")
      (node (ref "IC1") (pin "C3") (pinfunction "TSENSE_C3") (pintype "passive"))
    )
    (net (code "66") (name "unconnected-(IC1-TSW-PadB3)") (class "Default")
      (node (ref "IC1") (pin "B3") (pinfunction "TSW_B3") (pintype "output"))
    )
    (net (code "67") (name "unconnected-(IC2-IO35-Pad28)") (class "Default")
      (node (ref "IC2") (pin "28") (pinfunction "IO35_28") (pintype "bidirectional"))
    )
    (net (code "68") (name "unconnected-(IC2-IO36-Pad29)") (class "Default")
      (node (ref "IC2") (pin "29") (pinfunction "IO36_29") (pintype "bidirectional"))
    )
    (net (code "69") (name "unconnected-(IC2-IO37-Pad30)") (class "Default")
      (node (ref "IC2") (pin "30") (pinfunction "IO37_30") (pintype "bidirectional"))
    )
    (net (code "70") (name "unconnected-(IC2-IO45-Pad26)") (class "Default")
      (node (ref "IC2") (pin "26") (pinfunction "IO45_26") (pintype "bidirectional"))
    )
    (net (code "71") (name "unconnected-(IC2-IO46-Pad16)") (class "Default")
      (node (ref "IC2") (pin "16") (pinfunction "IO46_16") (pintype "bidirectional"))
    )
    (net (code "72") (name "unconnected-(JP1-Pad1)") (class "Default")
      (node (ref "JP1") (pin "1") (pinfunction "1_1") (pintype "passive"))
    )
    (net (code "73") (name "unconnected-(JP1-Pad2)") (class "Default")
      (node (ref "JP1") (pin "2") (pinfunction "2_2") (pintype "passive"))
    )
    (net (code "74") (name "unconnected-(JP1-Pad3)") (class "Default")
      (node (ref "JP1") (pin "3") (pinfunction "3_3") (pintype "passive"))
    )
    (net (code "75") (name "unconnected-(U2-P4-Pad4)") (class "Default")
      (node (ref "U2") (pin "4") (pinfunction "P4_4") (pintype "bidirectional"))
    )
    (net (code "76") (name "unconnected-(X3-SBU1-PadA8)") (class "Default")
      (node (ref "X3") (pin "A8") (pinfunction "SBU1_A8") (pintype "bidirectional"))
    )
    (net (code "77") (name "unconnected-(X3-SBU2-PadB8)") (class "Default")
      (node (ref "X3") (pin "B8") (pinfunction "SBU2_B8") (pintype "bidirectional"))
    )
  )
)
